# Exp_Board_Slolu_v0_2_1.net
KiCad netlist of a schematic drawn in EAGLE
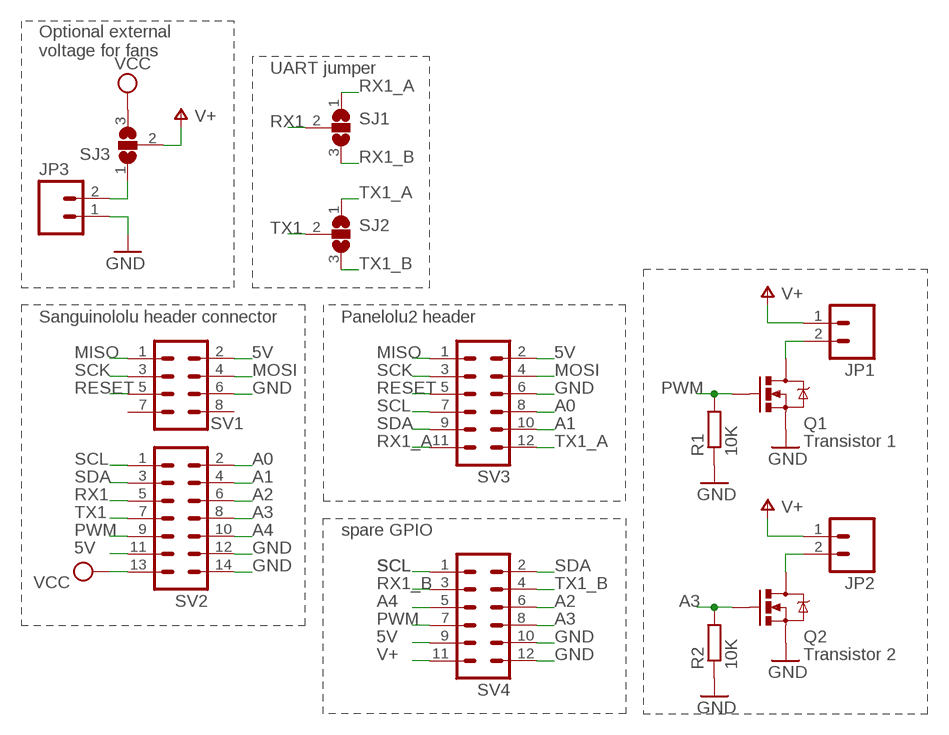
[diagram p0: schematic, sheet 1]

(export (version "E")
  (design (tool "Eeschema 10.0.6"))
  (components
    (comp (ref "JP1")
      (value "M02PTH")
      (footprint "eagle-import:1X02")
      (libsource (lib "eagle-import") (part "M02PTH"))
    )
    (comp (ref "JP2")
      (value "M02PTH")
      (footprint "eagle-import:1X02")
      (libsource (lib "eagle-import") (part "M02PTH"))
    )
    (comp (ref "JP3")
      (value "M02LOCK")
      (footprint "eagle-import:1X02_LOCK")
      (libsource (lib "eagle-import") (part "M02LOCK"))
    )
    (comp (ref "Q1")
      (value "Transistor 1")
      (footprint "eagle-import:TO220V")
      (libsource (lib "eagle-import") (part "MOSFET-NCHANNELPTH2"))
    )
    (comp (ref "Q2")
      (value "Transistor 2")
      (footprint "eagle-import:TO220V")
      (libsource (lib "eagle-import") (part "MOSFET-NCHANNELPTH2"))
    )
    (comp (ref "R1")
      (value "10K")
      (footprint "eagle-import:0204_7")
      (libsource (lib "eagle-import") (part "R-EU_0204/7"))
    )
    (comp (ref "R2")
      (value "10K")
      (footprint "eagle-import:0204_7")
      (libsource (lib "eagle-import") (part "R-EU_0204/7"))
    )
    (comp (ref "SJ1")
      (value "SJ2W")
      (footprint "eagle-import:SJ_2")
      (libsource (lib "eagle-import") (part "SJ2W"))
    )
    (comp (ref "SJ2")
      (value "SJ2W")
      (footprint "eagle-import:SJ_2")
      (libsource (lib "eagle-import") (part "SJ2W"))
    )
    (comp (ref "SJ3")
      (value "SJ2W")
      (footprint "eagle-import:SJ_2")
      (libsource (lib "eagle-import") (part "SJ2W"))
    )
    (comp (ref "SV1")
      (value "MA04-2")
      (footprint "eagle-import:MA04-2")
      (libsource (lib "eagle-import") (part "MA04-2"))
    )
    (comp (ref "SV2")
      (value "MA07-2")
      (footprint "eagle-import:MA07-2")
      (libsource (lib "eagle-import") (part "MA07-2"))
    )
    (comp (ref "SV3")
      (value "MA06-2")
      (footprint "eagle-import:MA06-2")
      (libsource (lib "eagle-import") (part "MA06-2"))
    )
    (comp (ref "SV4")
      (value "MA06-2")
      (footprint "eagle-import:MA06-2")
      (libsource (lib "eagle-import") (part "MA06-2"))
    )
  )
  (nets
    (net (code "1") (name "/5V") (class "Default")
      (node (ref "SV1") (pin "2") (pinfunction "2_2") (pintype "passive"))
      (node (ref "SV2") (pin "11") (pinfunction "11_11") (pintype "passive"))
      (node (ref "SV3") (pin "2") (pinfunction "2_2") (pintype "passive"))
      (node (ref "SV4") (pin "9") (pinfunction "9_9") (pintype "passive"))
    )
    (net (code "2") (name "/A0") (class "Default")
      (node (ref "SV2") (pin "2") (pinfunction "2_2") (pintype "passive"))
      (node (ref "SV3") (pin "8") (pinfunction "8_8") (pintype "passive"))
    )
    (net (code "3") (name "/A1") (class "Default")
      (node (ref "SV2") (pin "4") (pinfunction "4_4") (pintype "passive"))
      (node (ref "SV3") (pin "10") (pinfunction "10_10") (pintype "passive"))
    )
    (net (code "4") (name "/A2") (class "Default")
      (node (ref "SV2") (pin "6") (pinfunction "6_6") (pintype "passive"))
      (node (ref "SV4") (pin "6") (pinfunction "6_6") (pintype "passive"))
    )
    (net (code "5") (name "/A3") (class "Default")
      (node (ref "Q2") (pin "1") (pinfunction "G_1") (pintype "passive"))
      (node (ref "R2") (pin "2") (pinfunction "2_2") (pintype "passive"))
      (node (ref "SV2") (pin "8") (pinfunction "8_8") (pintype "passive"))
      (node (ref "SV4") (pin "8") (pinfunction "8_8") (pintype "passive"))
    )
    (net (code "6") (name "/A4") (class "Default")
      (node (ref "SV2") (pin "10") (pinfunction "10_10") (pintype "passive"))
      (node (ref "SV4") (pin "5") (pinfunction "5_5") (pintype "passive"))
    )
    (net (code "7") (name "/MISO") (class "Default")
      (node (ref "SV1") (pin "1") (pinfunction "1_1") (pintype "passive"))
      (node (ref "SV3") (pin "1") (pinfunction "1_1") (pintype "passive"))
    )
    (net (code "8") (name "/MOSI") (class "Default")
      (node (ref "SV1") (pin "4") (pinfunction "4_4") (pintype "passive"))
      (node (ref "SV3") (pin "4") (pinfunction "4_4") (pintype "passive"))
    )
    (net (code "9") (name "/PWM") (class "Default")
      (node (ref "Q1") (pin "1") (pinfunction "G_1") (pintype "passive"))
      (node (ref "R1") (pin "2") (pinfunction "2_2") (pintype "passive"))
      (node (ref "SV2") (pin "9") (pinfunction "9_9") (pintype "passive"))
      (node (ref "SV4") (pin "7") (pinfunction "7_7") (pintype "passive"))
    )
    (net (code "10") (name "/RESET") (class "Default")
      (node (ref "SV1") (pin "5") (pinfunction "5_5") (pintype "passive"))
      (node (ref "SV3") (pin "5") (pinfunction "5_5") (pintype "passive"))
    )
    (net (code "11") (name "/RX1") (class "Default")
      (node (ref "SJ1") (pin "2") (pinfunction "2_2") (pintype "passive"))
      (node (ref "SV2") (pin "5") (pinfunction "5_5") (pintype "passive"))
    )
    (net (code "12") (name "/RX1_A") (class "Default")
      (node (ref "SJ1") (pin "1") (pinfunction "1_1") (pintype "passive"))
      (node (ref "SV3") (pin "11") (pinfunction "11_11") (pintype "passive"))
    )
    (net (code "13") (name "/RX1_B") (class "Default")
      (node (ref "SJ1") (pin "3") (pinfunction "3_3") (pintype "passive"))
      (node (ref "SV4") (pin "3") (pinfunction "3_3") (pintype "passive"))
    )
    (net (code "14") (name "/SCK") (class "Default")
      (node (ref "SV1") (pin "3") (pinfunction "3_3") (pintype "passive"))
      (node (ref "SV3") (pin "3") (pinfunction "3_3") (pintype "passive"))
    )
    (net (code "15") (name "/SCL") (class "Default")
      (node (ref "SV2") (pin "1") (pinfunction "1_1") (pintype "passive"))
      (node (ref "SV3") (pin "7") (pinfunction "7_7") (pintype "passive"))
      (node (ref "SV4") (pin "1") (pinfunction "1_1") (pintype "passive"))
    )
    (net (code "16") (name "/SDA") (class "Default")
      (node (ref "SV2") (pin "3") (pinfunction "3_3") (pintype "passive"))
      (node (ref "SV3") (pin "9") (pinfunction "9_9") (pintype "passive"))
      (node (ref "SV4") (pin "2") (pinfunction "2_2") (pintype "passive"))
    )
    (net (code "17") (name "/TX1") (class "Default")
      (node (ref "SJ2") (pin "2") (pinfunction "2_2") (pintype "passive"))
      (node (ref "SV2") (pin "7") (pinfunction "7_7") (pintype "passive"))
    )
    (net (code "18") (name "/TX1_A") (class "Default")
      (node (ref "SJ2") (pin "1") (pinfunction "1_1") (pintype "passive"))
      (node (ref "SV3") (pin "12") (pinfunction "12_12") (pintype "passive"))
    )
    (net (code "19") (name "/TX1_B") (class "Default")
      (node (ref "SJ2") (pin "3") (pinfunction "3_3") (pintype "passive"))
      (node (ref "SV4") (pin "4") (pinfunction "4_4") (pintype "passive"))
    )
    (net (code "20") (name "GND") (class "Default")
      (node (ref "JP3") (pin "1") (pinfunction "1_1") (pintype "passive"))
      (node (ref "Q1") (pin "3") (pinfunction "S_3") (pintype "passive"))
      (node (ref "Q2") (pin "3") (pinfunction "S_3") (pintype "passive"))
      (node (ref "R1") (pin "1") (pinfunction "1_1") (pintype "passive"))
      (node (ref "R2") (pin "1") (pinfunction "1_1") (pintype "passive"))
      (node (ref "SV1") (pin "6") (pinfunction "6_6") (pintype "passive"))
      (node (ref "SV2") (pin "12") (pinfunction "12_12") (pintype "passive"))
      (node (ref "SV2") (pin "14") (pinfunction "14_14") (pintype "passive"))
      (node (ref "SV3") (pin "6") (pinfunction "6_6") (pintype "passive"))
      (node (ref "SV4") (pin "10") (pinfunction "10_10") (pintype "passive"))
      (node (ref "SV4") (pin "12") (pinfunction "12_12") (pintype "passive"))
    )
    (net (code "21") (name "Net-(JP3-Pad2)") (class "Default")
      (node (ref "JP3") (pin "2") (pinfunction "2_2") (pintype "passive"))
      (node (ref "SJ3") (pin "1") (pinfunction "1_1") (pintype "passive"))
    )
    (net (code "22") (name "Net-(Q1-D)") (class "Default")
      (node (ref "JP1") (pin "2") (pinfunction "2_2") (pintype "passive"))
      (node (ref "Q1") (pin "2") (pinfunction "D_2") (pintype "passive"))
    )
    (net (code "23") (name "Net-(Q2-D)") (class "Default")
      (node (ref "JP2") (pin "2") (pinfunction "2_2") (pintype "passive"))
      (node (ref "Q2") (pin "2") (pinfunction "D_2") (pintype "passive"))
    )
    (net (code "24") (name "V+") (class "Default")
      (node (ref "JP1") (pin "1") (pinfunction "1_1") (pintype "passive"))
      (node (ref "JP2") (pin "1") (pinfunction "1_1") (pintype "passive"))
      (node (ref "SJ3") (pin "2") (pinfunction "2_2") (pintype "passive"))
      (node (ref "SV4") (pin "11") (pinfunction "11_11") (pintype "passive"))
    )
    (net (code "25") (name "VCC") (class "Default")
      (node (ref "SJ3") (pin "3") (pinfunction "3_3") (pintype "passive"))
      (node (ref "SV2") (pin "13") (pinfunction "13_13") (pintype "passive"))
    )
    (net (code "26") (name "unconnected-(SV1-Pad7)") (class "Default")
      (node (ref "SV1") (pin "7") (pinfunction "7_7") (pintype "passive"))
    )
    (net (code "27") (name "unconnected-(SV1-Pad8)") (class "Default")
      (node (ref "SV1") (pin "8") (pinfunction "8_8") (pintype "passive"))
    )
  )
)
